# ATMega168-CAN.net
KiCad netlist of a schematic drawn in EAGLE
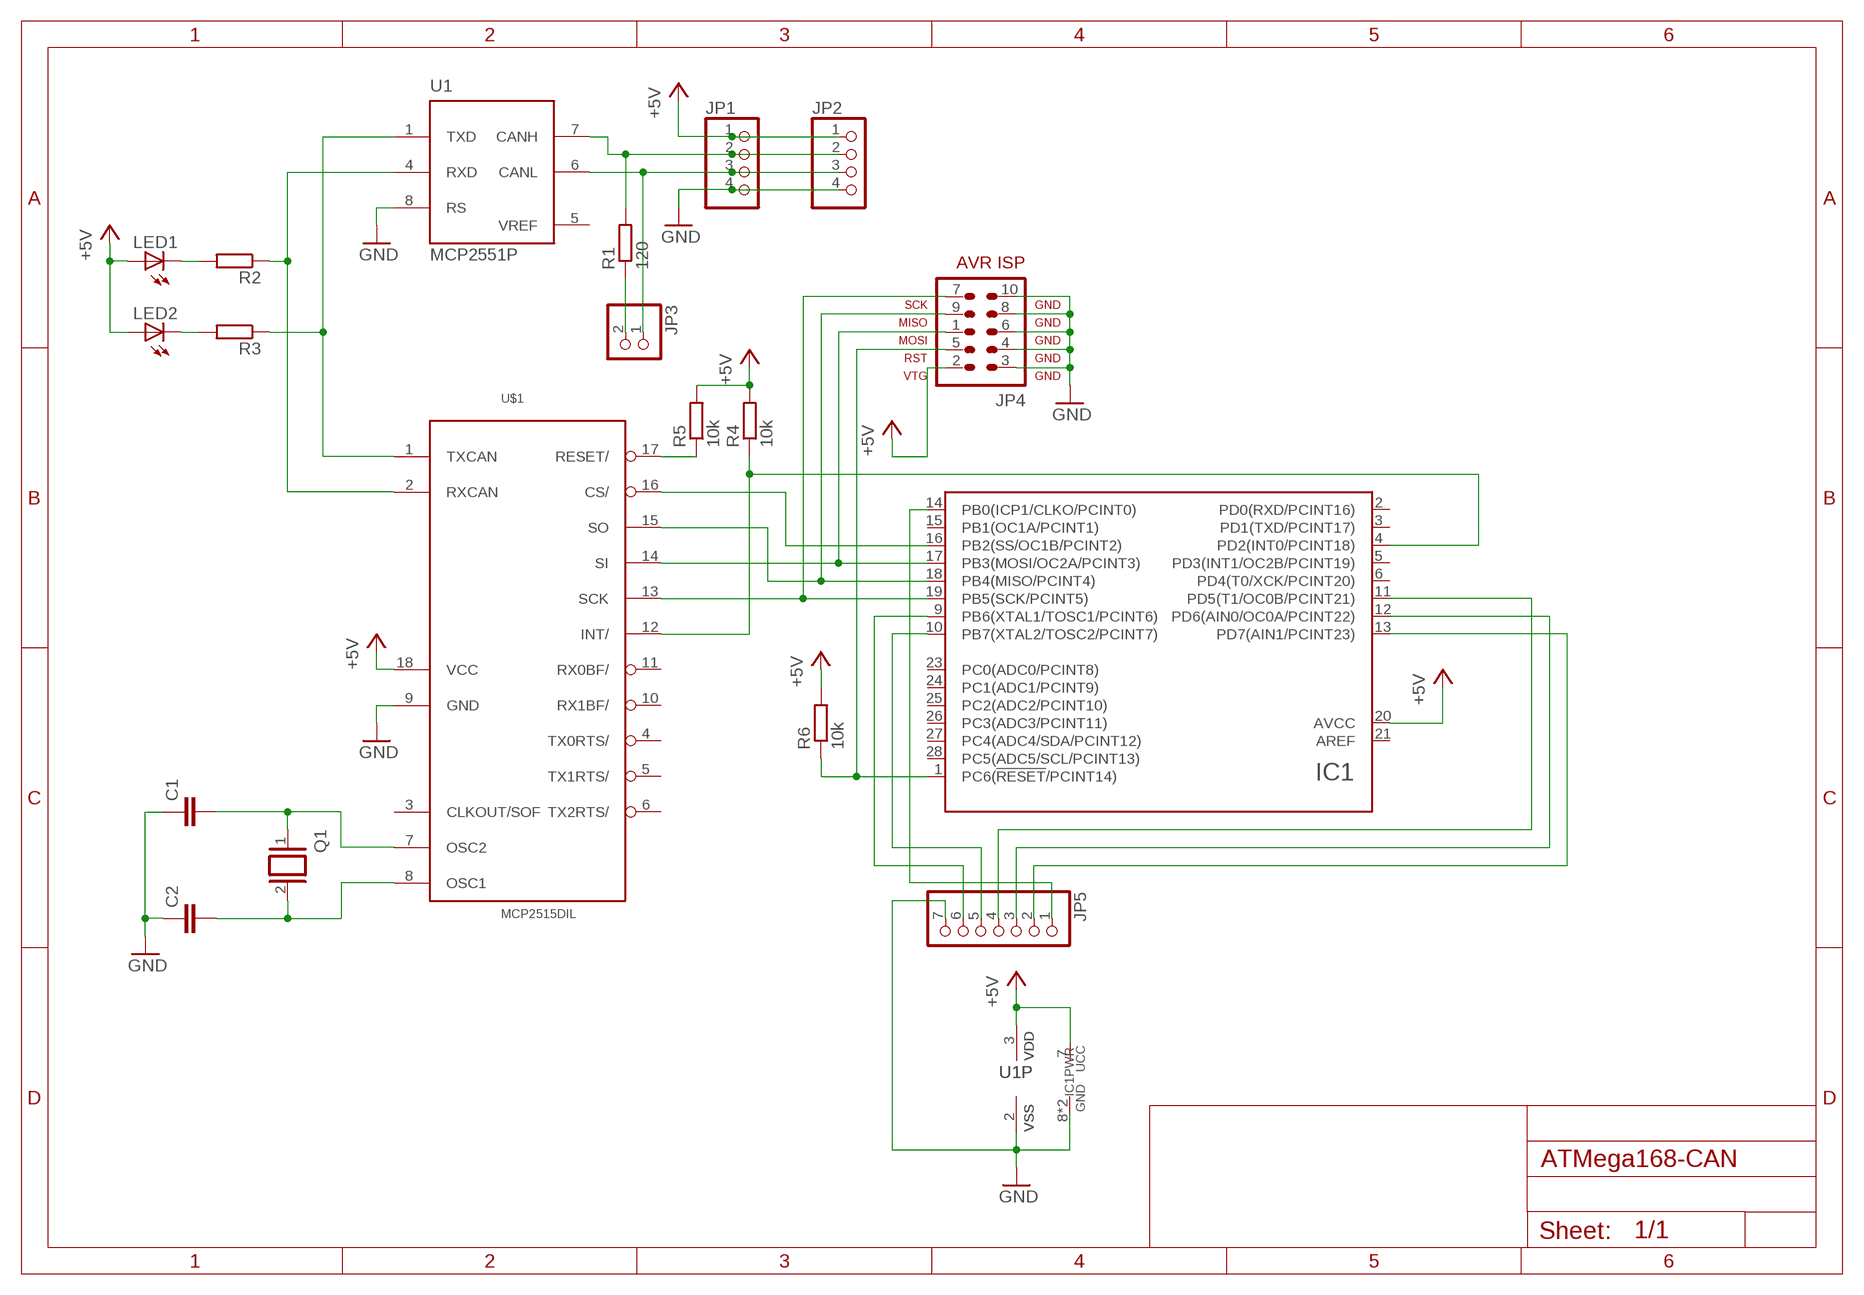
[diagram p0: schematic, sheet 1]

(export (version "E")
  (design (tool "Eeschema 10.0.6"))
  (components
    (comp (ref "C1")
      (value "C-EU025-024X044")
      (footprint "eagle-import:C025-024X044")
      (libsource (lib "eagle-import") (part "C-EU025-024X044"))
    )
    (comp (ref "C2")
      (value "C-EU025-024X044")
      (footprint "eagle-import:C025-024X044")
      (libsource (lib "eagle-import") (part "C-EU025-024X044"))
    )
    (comp (ref "IC1")
      (value "ATMEGA48/88/168/328-PU(DIP28)PU")
      (footprint "eagle-import:DIL28")
      (libsource (lib "eagle-import") (part "ATMEGA48/88/168/328-PU(DIP28)PU"))
    )
    (comp (ref "JP1")
      (value "PINHD-1X4/90")
      (footprint "eagle-import:1X04_90")
      (libsource (lib "eagle-import") (part "PINHD-1X4/90"))
    )
    (comp (ref "JP2")
      (value "PINHD-1X4/90")
      (footprint "eagle-import:1X04_90")
      (libsource (lib "eagle-import") (part "PINHD-1X4/90"))
    )
    (comp (ref "JP3")
      (value "PINHD-1X2")
      (footprint "eagle-import:1X02")
      (libsource (lib "eagle-import") (part "PINHD-1X2"))
    )
    (comp (ref "JP4")
      (value "AVR-ISP-10")
      (footprint "eagle-import:AVR-ISP-10")
      (libsource (lib "eagle-import") (part "AVR-ISP-10"))
    )
    (comp (ref "JP5")
      (value "PINHD-1X7")
      (footprint "eagle-import:1X07")
      (libsource (lib "eagle-import") (part "PINHD-1X7"))
    )
    (comp (ref "LED1")
      (value "LED5MM")
      (footprint "eagle-import:LED5MM")
      (libsource (lib "eagle-import") (part "LED5MM"))
    )
    (comp (ref "LED2")
      (value "LED5MM")
      (footprint "eagle-import:LED5MM")
      (libsource (lib "eagle-import") (part "LED5MM"))
    )
    (comp (ref "Q1")
      (value "XTAL/S")
      (footprint "eagle-import:QS")
      (libsource (lib "eagle-import") (part "XTAL/S"))
    )
    (comp (ref "R1")
      (value "120")
      (footprint "eagle-import:0207_10")
      (libsource (lib "eagle-import") (part "R-EU_0207/10"))
    )
    (comp (ref "R2")
      (value "R-EU_0207/10")
      (footprint "eagle-import:0207_10")
      (libsource (lib "eagle-import") (part "R-EU_0207/10"))
    )
    (comp (ref "R3")
      (value "R-EU_0207/10")
      (footprint "eagle-import:0207_10")
      (libsource (lib "eagle-import") (part "R-EU_0207/10"))
    )
    (comp (ref "R4")
      (value "10k")
      (footprint "eagle-import:0207_10")
      (libsource (lib "eagle-import") (part "R-EU_0207/10"))
    )
    (comp (ref "R5")
      (value "10k")
      (footprint "eagle-import:0207_10")
      (libsource (lib "eagle-import") (part "R-EU_0207/10"))
    )
    (comp (ref "R6")
      (value "10k")
      (footprint "eagle-import:0207_10")
      (libsource (lib "eagle-import") (part "R-EU_0207/10"))
    )
    (comp (ref "U$1")
      (value "MCP2515DIL")
      (footprint "eagle-import:DIL18")
      (libsource (lib "eagle-import") (part "MCP2515DIL"))
    )
    (comp (ref "U1")
      (value "MCP2551P")
      (footprint "eagle-import:DIL8")
      (libsource (lib "eagle-import") (part "MCP2551P"))
    )
  )
  (nets
    (net (code "1") (name "+5V") (class "Default")
      (node (ref "IC1") (pin "20") (pinfunction "AVCC_20") (pintype "power_in"))
      (node (ref "IC1") (pin "7") (pinfunction "UCC_7") (pintype "power_in"))
      (node (ref "JP1") (pin "1") (pinfunction "1_1") (pintype "passive"))
      (node (ref "JP2") (pin "1") (pinfunction "1_1") (pintype "passive"))
      (node (ref "JP4") (pin "2") (pinfunction "2_2") (pintype "passive"))
      (node (ref "LED1") (pin "A") (pinfunction "A_A") (pintype "passive"))
      (node (ref "LED2") (pin "A") (pinfunction "A_A") (pintype "passive"))
      (node (ref "R4") (pin "2") (pinfunction "2_2") (pintype "passive"))
      (node (ref "R5") (pin "2") (pinfunction "2_2") (pintype "passive"))
      (node (ref "R6") (pin "2") (pinfunction "2_2") (pintype "passive"))
      (node (ref "U$1") (pin "18") (pinfunction "VCC_18") (pintype "power_in"))
      (node (ref "U1") (pin "3") (pinfunction "VDD_3") (pintype "power_in"))
    )
    (net (code "2") (name "/VREF") (class "Default")
      (node (ref "U1") (pin "5") (pinfunction "VREF_5") (pintype "power_in"))
    )
    (net (code "3") (name "GND") (class "Default")
      (node (ref "C1") (pin "1") (pinfunction "1_1") (pintype "passive"))
      (node (ref "C2") (pin "1") (pinfunction "1_1") (pintype "passive"))
      (node (ref "IC1") (pin "22") (pinfunction "GND_22") (pintype "power_in"))
      (node (ref "IC1") (pin "8") (pinfunction "GND_8") (pintype "power_in"))
      (node (ref "JP1") (pin "4") (pinfunction "4_4") (pintype "passive"))
      (node (ref "JP2") (pin "4") (pinfunction "4_4") (pintype "passive"))
      (node (ref "JP4") (pin "10") (pinfunction "10_10") (pintype "passive"))
      (node (ref "JP4") (pin "3") (pinfunction "3_3") (pintype "passive"))
      (node (ref "JP4") (pin "4") (pinfunction "4_4") (pintype "passive"))
      (node (ref "JP4") (pin "6") (pinfunction "6_6") (pintype "passive"))
      (node (ref "JP4") (pin "8") (pinfunction "8_8") (pintype "passive"))
      (node (ref "JP5") (pin "7") (pinfunction "7_7") (pintype "passive"))
      (node (ref "U$1") (pin "9") (pinfunction "GND_9") (pintype "power_in"))
      (node (ref "U1") (pin "2") (pinfunction "VSS_2") (pintype "power_in"))
      (node (ref "U1") (pin "8") (pinfunction "RS_8") (pintype "input"))
    )
    (net (code "4") (name "Net-(IC1A-PB0(ICP1{slash}CLKO{slash}PCINT0))") (class "Default")
      (node (ref "IC1") (pin "14") (pinfunction "PB0(ICP1/CLKO/PCINT0)_14") (pintype "bidirectional"))
      (node (ref "JP5") (pin "1") (pinfunction "1_1") (pintype "passive"))
    )
    (net (code "5") (name "Net-(IC1A-PB2(SS{slash}OC1B{slash}PCINT2))") (class "Default")
      (node (ref "IC1") (pin "16") (pinfunction "PB2(SS/OC1B/PCINT2)_16") (pintype "bidirectional"))
      (node (ref "U$1") (pin "16") (pinfunction "CS/_16") (pintype "input"))
    )
    (net (code "6") (name "Net-(IC1A-PB3(MOSI{slash}OC2A{slash}PCINT3))") (class "Default")
      (node (ref "IC1") (pin "17") (pinfunction "PB3(MOSI/OC2A/PCINT3)_17") (pintype "bidirectional"))
      (node (ref "JP4") (pin "1") (pinfunction "1_1") (pintype "passive"))
      (node (ref "U$1") (pin "14") (pinfunction "SI_14") (pintype "input"))
    )
    (net (code "7") (name "Net-(IC1A-PB4(MISO{slash}PCINT4))") (class "Default")
      (node (ref "IC1") (pin "18") (pinfunction "PB4(MISO/PCINT4)_18") (pintype "bidirectional"))
      (node (ref "JP4") (pin "9") (pinfunction "9_9") (pintype "passive"))
      (node (ref "U$1") (pin "15") (pinfunction "SO_15") (pintype "output"))
    )
    (net (code "8") (name "Net-(IC1A-PB5(SCK{slash}PCINT5))") (class "Default")
      (node (ref "IC1") (pin "19") (pinfunction "PB5(SCK/PCINT5)_19") (pintype "bidirectional"))
      (node (ref "JP4") (pin "7") (pinfunction "7_7") (pintype "passive"))
      (node (ref "U$1") (pin "13") (pinfunction "SCK_13") (pintype "input"))
    )
    (net (code "9") (name "Net-(IC1A-PB6(XTAL1{slash}TOSC1{slash}PCINT6))") (class "Default")
      (node (ref "IC1") (pin "9") (pinfunction "PB6(XTAL1/TOSC1/PCINT6)_9") (pintype "bidirectional"))
      (node (ref "JP5") (pin "6") (pinfunction "6_6") (pintype "passive"))
    )
    (net (code "10") (name "Net-(IC1A-PB7(XTAL2{slash}TOSC2{slash}PCINT7))") (class "Default")
      (node (ref "IC1") (pin "10") (pinfunction "PB7(XTAL2/TOSC2/PCINT7)_10") (pintype "bidirectional"))
      (node (ref "JP5") (pin "5") (pinfunction "5_5") (pintype "passive"))
    )
    (net (code "11") (name "Net-(IC1A-PC6(~{RESET}{slash}PCINT14))") (class "Default")
      (node (ref "IC1") (pin "1") (pinfunction "PC6(~{RESET}/PCINT14)_1") (pintype "bidirectional"))
      (node (ref "JP4") (pin "5") (pinfunction "5_5") (pintype "passive"))
      (node (ref "R6") (pin "1") (pinfunction "1_1") (pintype "passive"))
    )
    (net (code "12") (name "Net-(IC1A-PD2(INT0{slash}PCINT18))") (class "Default")
      (node (ref "IC1") (pin "4") (pinfunction "PD2(INT0/PCINT18)_4") (pintype "bidirectional"))
      (node (ref "R4") (pin "1") (pinfunction "1_1") (pintype "passive"))
      (node (ref "U$1") (pin "12") (pinfunction "INT/_12") (pintype "output"))
    )
    (net (code "13") (name "Net-(IC1A-PD5(T1{slash}OC0B{slash}PCINT21))") (class "Default")
      (node (ref "IC1") (pin "11") (pinfunction "PD5(T1/OC0B/PCINT21)_11") (pintype "bidirectional"))
      (node (ref "JP5") (pin "4") (pinfunction "4_4") (pintype "passive"))
    )
    (net (code "14") (name "Net-(IC1A-PD6(AIN0{slash}OC0A{slash}PCINT22))") (class "Default")
      (node (ref "IC1") (pin "12") (pinfunction "PD6(AIN0/OC0A/PCINT22)_12") (pintype "bidirectional"))
      (node (ref "JP5") (pin "3") (pinfunction "3_3") (pintype "passive"))
    )
    (net (code "15") (name "Net-(IC1A-PD7(AIN1{slash}PCINT23))") (class "Default")
      (node (ref "IC1") (pin "13") (pinfunction "PD7(AIN1/PCINT23)_13") (pintype "bidirectional"))
      (node (ref "JP5") (pin "2") (pinfunction "2_2") (pintype "passive"))
    )
    (net (code "16") (name "Net-(JP3-Pad2)") (class "Default")
      (node (ref "JP3") (pin "2") (pinfunction "2_2") (pintype "passive"))
      (node (ref "R1") (pin "1") (pinfunction "1_1") (pintype "passive"))
    )
    (net (code "17") (name "Net-(LED1-C)") (class "Default")
      (node (ref "LED1") (pin "K") (pinfunction "C_K") (pintype "passive"))
      (node (ref "R2") (pin "2") (pinfunction "2_2") (pintype "passive"))
    )
    (net (code "18") (name "Net-(LED2-C)") (class "Default")
      (node (ref "LED2") (pin "K") (pinfunction "C_K") (pintype "passive"))
      (node (ref "R3") (pin "2") (pinfunction "2_2") (pintype "passive"))
    )
    (net (code "19") (name "Net-(U$1-OSC1)") (class "Default")
      (node (ref "C2") (pin "2") (pinfunction "2_2") (pintype "passive"))
      (node (ref "Q1") (pin "2") (pinfunction "2_2") (pintype "passive"))
      (node (ref "U$1") (pin "8") (pinfunction "OSC1_8") (pintype "bidirectional"))
    )
    (net (code "20") (name "Net-(U$1-OSC2)") (class "Default")
      (node (ref "C1") (pin "2") (pinfunction "2_2") (pintype "passive"))
      (node (ref "Q1") (pin "1") (pinfunction "1_1") (pintype "passive"))
      (node (ref "U$1") (pin "7") (pinfunction "OSC2_7") (pintype "bidirectional"))
    )
    (net (code "21") (name "Net-(U$1-RESET{slash})") (class "Default")
      (node (ref "R5") (pin "1") (pinfunction "1_1") (pintype "passive"))
      (node (ref "U$1") (pin "17") (pinfunction "RESET/_17") (pintype "input"))
    )
    (net (code "22") (name "Net-(U$1-RXCAN)") (class "Default")
      (node (ref "R2") (pin "1") (pinfunction "1_1") (pintype "passive"))
      (node (ref "U$1") (pin "2") (pinfunction "RXCAN_2") (pintype "input"))
      (node (ref "U1") (pin "4") (pinfunction "RXD_4") (pintype "output"))
    )
    (net (code "23") (name "Net-(U$1-TXCAN)") (class "Default")
      (node (ref "R3") (pin "1") (pinfunction "1_1") (pintype "passive"))
      (node (ref "U$1") (pin "1") (pinfunction "TXCAN_1") (pintype "output"))
      (node (ref "U1") (pin "1") (pinfunction "TXD_1") (pintype "input"))
    )
    (net (code "24") (name "Net-(U1A-CANH)") (class "Default")
      (node (ref "JP1") (pin "2") (pinfunction "2_2") (pintype "passive"))
      (node (ref "JP2") (pin "2") (pinfunction "2_2") (pintype "passive"))
      (node (ref "R1") (pin "2") (pinfunction "2_2") (pintype "passive"))
      (node (ref "U1") (pin "7") (pinfunction "CANH_7") (pintype "bidirectional"))
    )
    (net (code "25") (name "Net-(U1A-CANL)") (class "Default")
      (node (ref "JP1") (pin "3") (pinfunction "3_3") (pintype "passive"))
      (node (ref "JP2") (pin "3") (pinfunction "3_3") (pintype "passive"))
      (node (ref "JP3") (pin "1") (pinfunction "1_1") (pintype "passive"))
      (node (ref "U1") (pin "6") (pinfunction "CANL_6") (pintype "bidirectional"))
    )
    (net (code "26") (name "unconnected-(IC1A-AREF-Pad21)") (class "Default")
      (node (ref "IC1") (pin "21") (pinfunction "AREF_21") (pintype "passive"))
    )
    (net (code "27") (name "unconnected-(IC1A-PB1(OC1A{slash}PCINT1)-Pad15)") (class "Default")
      (node (ref "IC1") (pin "15") (pinfunction "PB1(OC1A/PCINT1)_15") (pintype "bidirectional"))
    )
    (net (code "28") (name "unconnected-(IC1A-PC0(ADC0{slash}PCINT8)-Pad23)") (class "Default")
      (node (ref "IC1") (pin "23") (pinfunction "PC0(ADC0/PCINT8)_23") (pintype "bidirectional"))
    )
    (net (code "29") (name "unconnected-(IC1A-PC1(ADC1{slash}PCINT9)-Pad24)") (class "Default")
      (node (ref "IC1") (pin "24") (pinfunction "PC1(ADC1/PCINT9)_24") (pintype "bidirectional"))
    )
    (net (code "30") (name "unconnected-(IC1A-PC2(ADC2{slash}PCINT10)-Pad25)") (class "Default")
      (node (ref "IC1") (pin "25") (pinfunction "PC2(ADC2/PCINT10)_25") (pintype "bidirectional"))
    )
    (net (code "31") (name "unconnected-(IC1A-PC3(ADC3{slash}PCINT11)-Pad26)") (class "Default")
      (node (ref "IC1") (pin "26") (pinfunction "PC3(ADC3/PCINT11)_26") (pintype "bidirectional"))
    )
    (net (code "32") (name "unconnected-(IC1A-PC4(ADC4{slash}SDA{slash}PCINT12)-Pad27)") (class "Default")
      (node (ref "IC1") (pin "27") (pinfunction "PC4(ADC4/SDA/PCINT12)_27") (pintype "bidirectional"))
    )
    (net (code "33") (name "unconnected-(IC1A-PC5(ADC5{slash}SCL{slash}PCINT13)-Pad28)") (class "Default")
      (node (ref "IC1") (pin "28") (pinfunction "PC5(ADC5/SCL/PCINT13)_28") (pintype "bidirectional"))
    )
    (net (code "34") (name "unconnected-(IC1A-PD0(RXD{slash}PCINT16)-Pad2)") (class "Default")
      (node (ref "IC1") (pin "2") (pinfunction "PD0(RXD/PCINT16)_2") (pintype "bidirectional"))
    )
    (net (code "35") (name "unconnected-(IC1A-PD1(TXD{slash}PCINT17)-Pad3)") (class "Default")
      (node (ref "IC1") (pin "3") (pinfunction "PD1(TXD/PCINT17)_3") (pintype "bidirectional"))
    )
    (net (code "36") (name "unconnected-(IC1A-PD3(INT1{slash}OC2B{slash}PCINT19)-Pad5)") (class "Default")
      (node (ref "IC1") (pin "5") (pinfunction "PD3(INT1/OC2B/PCINT19)_5") (pintype "bidirectional"))
    )
    (net (code "37") (name "unconnected-(IC1A-PD4(T0{slash}XCK{slash}PCINT20)-Pad6)") (class "Default")
      (node (ref "IC1") (pin "6") (pinfunction "PD4(T0/XCK/PCINT20)_6") (pintype "bidirectional"))
    )
    (net (code "38") (name "unconnected-(U$1-CLKOUT{slash}SOF-Pad3)") (class "Default")
      (node (ref "U$1") (pin "3") (pinfunction "CLKOUT/SOF_3") (pintype "bidirectional"))
    )
    (net (code "39") (name "unconnected-(U$1-RX0BF{slash}-Pad11)") (class "Default")
      (node (ref "U$1") (pin "11") (pinfunction "RX0BF/_11") (pintype "bidirectional"))
    )
    (net (code "40") (name "unconnected-(U$1-RX1BF{slash}-Pad10)") (class "Default")
      (node (ref "U$1") (pin "10") (pinfunction "RX1BF/_10") (pintype "bidirectional"))
    )
    (net (code "41") (name "unconnected-(U$1-TX0RTS{slash}-Pad4)") (class "Default")
      (node (ref "U$1") (pin "4") (pinfunction "TX0RTS/_4") (pintype "bidirectional"))
    )
    (net (code "42") (name "unconnected-(U$1-TX1RTS{slash}-Pad5)") (class "Default")
      (node (ref "U$1") (pin "5") (pinfunction "TX1RTS/_5") (pintype "bidirectional"))
    )
    (net (code "43") (name "unconnected-(U$1-TX2RTS{slash}-Pad6)") (class "Default")
      (node (ref "U$1") (pin "6") (pinfunction "TX2RTS/_6") (pintype "bidirectional"))
    )
  )
)
